# Alim.net
KiCad netlist of a schematic drawn in Altium Designer
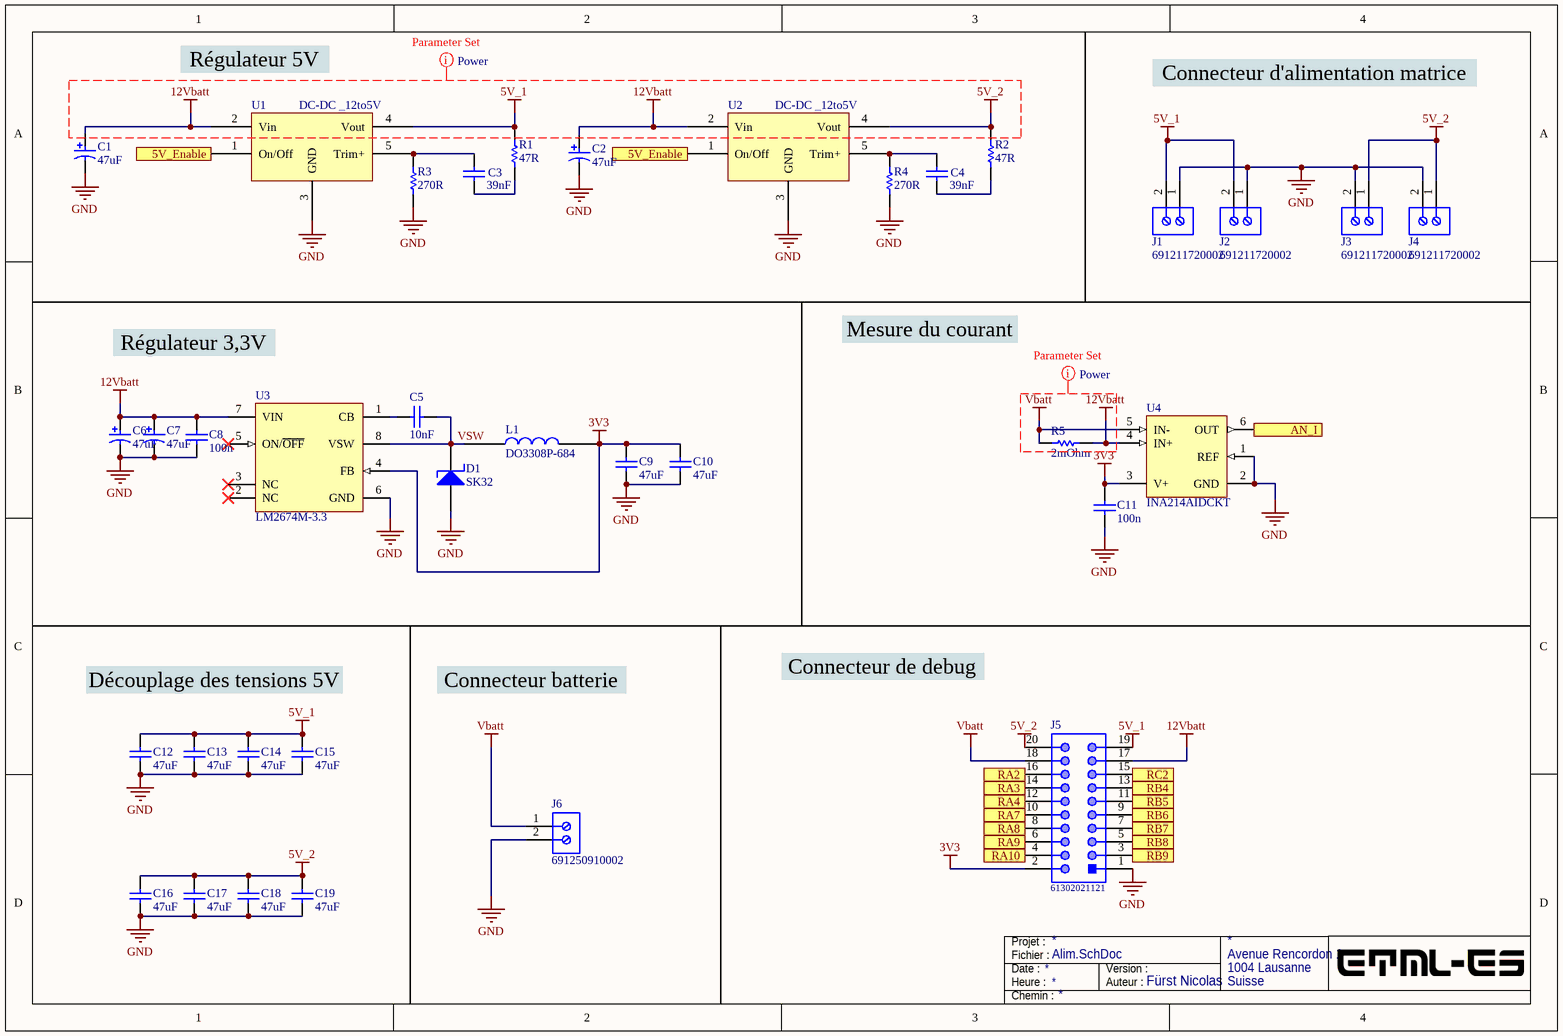
[diagram p0: Alim.SchDoc]

(export (version "E")
  (design (tool "Eeschema 10.0.6"))
  (components
    (comp (ref "C1")
      (value "47uF")
      (footprint "Capacitor")
      (fields (field (name "TOLERANCE") "20%") (field (name "MANUFACTURER") "Panasonic"))
      (libsource (lib "Schlib1") (part "CMP-2000-06221-1"))
    )
    (comp (ref "C2")
      (value "47uF")
      (footprint "Capacitor")
      (fields (field (name "TOLERANCE") "20%") (field (name "MANUFACTURER") "Panasonic"))
      (libsource (lib "Schlib1") (part "CMP-2000-06221-1"))
    )
    (comp (ref "C3")
      (value "39nF")
      (footprint "CAPC0805(2012)155_L")
      (fields (field (name "TOLERANCE") "Â±10%"))
      (libsource (lib "Schlib1") (part "Capa"))
    )
    (comp (ref "C4")
      (value "39nF")
      (footprint "CAPC0805(2012)155_L")
      (fields (field (name "TOLERANCE") "Â±10%"))
      (libsource (lib "Schlib1") (part "Capa"))
    )
    (comp (ref "C5")
      (value "10nF")
      (footprint "CAPC0805(2012)155_L")
      (fields (field (name "TOLERANCE") "Â±10%"))
      (libsource (lib "Schlib1") (part "Capa"))
    )
    (comp (ref "C6")
      (value "47uF")
      (footprint "Capacitor")
      (fields (field (name "TOLERANCE") "20%") (field (name "MANUFACTURER") "Panasonic"))
      (libsource (lib "Schlib1") (part "CMP-2000-06221-1"))
    )
    (comp (ref "C7")
      (value "47uF")
      (footprint "Capacitor")
      (fields (field (name "TOLERANCE") "20%") (field (name "MANUFACTURER") "Panasonic"))
      (libsource (lib "Schlib1") (part "CMP-2000-06221-1"))
    )
    (comp (ref "C8")
      (value "100n")
      (footprint "CAPC0805(2012)155_L")
      (fields (field (name "TOLERANCE") "Â±10%"))
      (libsource (lib "Schlib1") (part "Capa"))
    )
    (comp (ref "C9")
      (value "47uF")
      (footprint "CAPC1206(3216)190_N")
      (description "CAP 47uF 10V ±20% 1206 (3216 Metric) Thickness 1.9mm SMD")
      (fields (field (name "TOLERANCE") "Â±20%"))
      (libsource (lib "Altium Content Vault") (part "CAP"))
    )
    (comp (ref "C10")
      (value "47uF")
      (footprint "CAPC1206(3216)190_N")
      (description "CAP 47uF 10V ±20% 1206 (3216 Metric) Thickness 1.9mm SMD")
      (fields (field (name "TOLERANCE") "Â±20%"))
      (libsource (lib "Altium Content Vault") (part "CAP"))
    )
    (comp (ref "C11")
      (value "100n")
      (footprint "CAPC0805(2012)155_L")
      (fields (field (name "TOLERANCE") "Â±10%"))
      (libsource (lib "Schlib1") (part "Capa"))
    )
    (comp (ref "C12")
      (value "47uF")
      (footprint "CAPC1206(3216)190_N")
      (description "CAP 47uF 10V ±20% 1206 (3216 Metric) Thickness 1.9mm SMD")
      (fields (field (name "TOLERANCE") "Â±20%"))
      (libsource (lib "Altium Content Vault") (part "CAP"))
    )
    (comp (ref "C13")
      (value "47uF")
      (footprint "CAPC1206(3216)190_N")
      (description "CAP 47uF 10V ±20% 1206 (3216 Metric) Thickness 1.9mm SMD")
      (fields (field (name "TOLERANCE") "Â±20%"))
      (libsource (lib "Altium Content Vault") (part "CAP"))
    )
    (comp (ref "C14")
      (value "47uF")
      (footprint "CAPC1206(3216)190_N")
      (description "CAP 47uF 10V ±20% 1206 (3216 Metric) Thickness 1.9mm SMD")
      (fields (field (name "TOLERANCE") "Â±20%"))
      (libsource (lib "Altium Content Vault") (part "CAP"))
    )
    (comp (ref "C15")
      (value "47uF")
      (footprint "CAPC1206(3216)190_N")
      (description "CAP 47uF 10V ±20% 1206 (3216 Metric) Thickness 1.9mm SMD")
      (fields (field (name "TOLERANCE") "Â±20%"))
      (libsource (lib "Altium Content Vault") (part "CAP"))
    )
    (comp (ref "C16")
      (value "47uF")
      (footprint "CAPC1206(3216)190_N")
      (description "CAP 47uF 10V ±20% 1206 (3216 Metric) Thickness 1.9mm SMD")
      (fields (field (name "TOLERANCE") "Â±20%"))
      (libsource (lib "Altium Content Vault") (part "CAP"))
    )
    (comp (ref "C17")
      (value "47uF")
      (footprint "CAPC1206(3216)190_N")
      (description "CAP 47uF 10V ±20% 1206 (3216 Metric) Thickness 1.9mm SMD")
      (fields (field (name "TOLERANCE") "Â±20%"))
      (libsource (lib "Altium Content Vault") (part "CAP"))
    )
    (comp (ref "C18")
      (value "47uF")
      (footprint "CAPC1206(3216)190_N")
      (description "CAP 47uF 10V ±20% 1206 (3216 Metric) Thickness 1.9mm SMD")
      (fields (field (name "TOLERANCE") "Â±20%"))
      (libsource (lib "Altium Content Vault") (part "CAP"))
    )
    (comp (ref "C19")
      (value "47uF")
      (footprint "CAPC1206(3216)190_N")
      (description "CAP 47uF 10V ±20% 1206 (3216 Metric) Thickness 1.9mm SMD")
      (fields (field (name "TOLERANCE") "Â±20%"))
      (libsource (lib "Altium Content Vault") (part "CAP"))
    )
    (comp (ref "D1")
      (value "SK32")
      (footprint "DO-214AC")
      (description "Shotky diod")
      (fields (field (name "PARTNUMBER") "151031SS04000") (field (name "MANUFACTURER") "Wuerth Elektronik"))
      (libsource (lib "Schlib1") (part "SK32"))
    )
    (comp (ref "J1")
      (value "691211720002")
      (footprint "691211720002")
      (description "Serie 211 - 5.00 mm 45deg Entry Modular with Rising Cage Clamp - 15.50 mm Height WR-TBL, 2 pin")
      (fields (field (name "MANUFACTURER") "Wurth Elektronik") (field (name "PUBLISHER") "WurthElektronik"))
      (libsource (lib "Altium Content Vault") (part "WE-CN-1P-F-TB2"))
    )
    (comp (ref "J2")
      (value "691211720002")
      (footprint "691211720002")
      (description "Serie 211 - 5.00 mm 45deg Entry Modular with Rising Cage Clamp - 15.50 mm Height WR-TBL, 2 pin")
      (fields (field (name "MANUFACTURER") "Wurth Elektronik") (field (name "PUBLISHER") "WurthElektronik"))
      (libsource (lib "Altium Content Vault") (part "WE-CN-1P-F-TB2"))
    )
    (comp (ref "J3")
      (value "691211720002")
      (footprint "691211720002")
      (description "Serie 211 - 5.00 mm 45deg Entry Modular with Rising Cage Clamp - 15.50 mm Height WR-TBL, 2 pin")
      (fields (field (name "MANUFACTURER") "Wurth Elektronik") (field (name "PUBLISHER") "WurthElektronik"))
      (libsource (lib "Altium Content Vault") (part "WE-CN-1P-F-TB2"))
    )
    (comp (ref "J4")
      (value "691211720002")
      (footprint "691211720002")
      (description "Serie 211 - 5.00 mm 45deg Entry Modular with Rising Cage Clamp - 15.50 mm Height WR-TBL, 2 pin")
      (fields (field (name "MANUFACTURER") "Wurth Elektronik") (field (name "PUBLISHER") "WurthElektronik"))
      (libsource (lib "Altium Content Vault") (part "WE-CN-1P-F-TB2"))
    )
    (comp (ref "J5")
      (value "61302021121")
      (footprint "61302021121")
      (description "THT Vertical Pin Header WR-PHD, Pitch 2.54 mm, Dual Row, 20 pins")
      (fields (field (name "MANUFACTURER") "Wurth Elektronik") (field (name "PUBLISHER") "WurthElektronik"))
      (libsource (lib "Altium Content Vault") (part "WE-CN-2P-M-R20"))
    )
    (comp (ref "J6")
      (value "691250910002")
      (footprint "691250910002")
      (description "Serie 2509 - 9.52 mm Horizontal Entry Modular with Rising Cage Clamp WR-TBL, 2 pin")
      (fields (field (name "MANUFACTURER") "Wurth Elektronik") (field (name "PUBLISHER") "WurthElektronik"))
      (libsource (lib "Altium Content Vault") (part "WE-CN-1P-F-TB2"))
    )
    (comp (ref "L1")
      (value "DO3308P-684")
      (footprint "DO3308P")
      (libsource (lib "Schlib1") (part "DO3308P-684"))
    )
    (comp (ref "R1")
      (value "47R")
      (footprint "RESC0805(2012)_N")
      (fields (field (name "POWER") "0.125 W") (field (name "TOLERANCE") "1 %"))
      (libsource (lib "Schlib1") (part "Resistor"))
    )
    (comp (ref "R2")
      (value "47R")
      (footprint "RESC0805(2012)_N")
      (fields (field (name "POWER") "0.125 W") (field (name "TOLERANCE") "1 %"))
      (libsource (lib "Schlib1") (part "Resistor"))
    )
    (comp (ref "R3")
      (value "270R")
      (footprint "RESC0805(2012)_N")
      (fields (field (name "POWER") "0.125 W") (field (name "TOLERANCE") "1 %"))
      (libsource (lib "Schlib1") (part "Resistor"))
    )
    (comp (ref "R4")
      (value "270R")
      (footprint "RESC0805(2012)_N")
      (fields (field (name "POWER") "0.125 W") (field (name "TOLERANCE") "1 %"))
      (libsource (lib "Schlib1") (part "Resistor"))
    )
    (comp (ref "R5")
      (value "2mOhm")
      (footprint "RESC1206(3216)_N")
      (fields (field (name "POWER") "0.125 W") (field (name "TOLERANCE") "1 %"))
      (libsource (lib "Schlib1") (part "Resistor"))
    )
    (comp (ref "U1")
      (value "DC-DC _12to5V")
      (footprint "DC-DC")
      (libsource (lib "Schlib1") (part "DC-DC _12to5V"))
    )
    (comp (ref "U2")
      (value "DC-DC _12to5V")
      (footprint "DC-DC")
      (libsource (lib "Schlib1") (part "DC-DC _12to5V"))
    )
    (comp (ref "U3")
      (value "LM2674M-3.3")
      (footprint "M08A_N")
      (fields (field (name "MANUFACTURER") "National Semiconductor"))
      (libsource (lib "Altium Content Vault") (part "PM-REG-LM2674"))
    )
    (comp (ref "U4")
      (value "INA214AIDCKT")
      (footprint "DCK0006A_N")
      (fields (field (name "MANUFACTURER") "TexasInstruments"))
      (libsource (lib "Schlib1") (part "CMP-2000-06456-1"))
    )
  )
  (nets
    (net (code "1") (name "/5V_Enable") (class "Default")
      (node (ref "U1") (pin "1") (pinfunction "On/Off_1") (pintype "passive"))
      (node (ref "U2") (pin "1") (pinfunction "On/Off_1") (pintype "passive"))
    )
    (net (code "2") (name "/AN_I") (class "Default")
      (node (ref "U4") (pin "6") (pinfunction "OUT_6") (pintype "output"))
    )
    (net (code "3") (name "/RA2") (class "Default")
      (node (ref "J5") (pin "16") (pinfunction "16_16") (pintype "passive"))
    )
    (net (code "4") (name "/RA3") (class "Default")
      (node (ref "J5") (pin "14") (pinfunction "14_14") (pintype "passive"))
    )
    (net (code "5") (name "/RA4") (class "Default")
      (node (ref "J5") (pin "12") (pinfunction "12_12") (pintype "passive"))
    )
    (net (code "6") (name "/RA7") (class "Default")
      (node (ref "J5") (pin "10") (pinfunction "10_10") (pintype "passive"))
    )
    (net (code "7") (name "/RA8") (class "Default")
      (node (ref "J5") (pin "8") (pinfunction "8_8") (pintype "passive"))
    )
    (net (code "8") (name "/RA9") (class "Default")
      (node (ref "J5") (pin "6") (pinfunction "6_6") (pintype "passive"))
    )
    (net (code "9") (name "/RA10") (class "Default")
      (node (ref "J5") (pin "4") (pinfunction "4_4") (pintype "passive"))
    )
    (net (code "10") (name "/RB4") (class "Default")
      (node (ref "J5") (pin "13") (pinfunction "13_13") (pintype "passive"))
    )
    (net (code "11") (name "/RB5") (class "Default")
      (node (ref "J5") (pin "11") (pinfunction "11_11") (pintype "passive"))
    )
    (net (code "12") (name "/RB6") (class "Default")
      (node (ref "J5") (pin "9") (pinfunction "9_9") (pintype "passive"))
    )
    (net (code "13") (name "/RB7") (class "Default")
      (node (ref "J5") (pin "7") (pinfunction "7_7") (pintype "passive"))
    )
    (net (code "14") (name "/RB8") (class "Default")
      (node (ref "J5") (pin "5") (pinfunction "5_5") (pintype "passive"))
    )
    (net (code "15") (name "/RB9") (class "Default")
      (node (ref "J5") (pin "3") (pinfunction "3_3") (pintype "passive"))
    )
    (net (code "16") (name "/RC2") (class "Default")
      (node (ref "J5") (pin "15") (pinfunction "15_15") (pintype "passive"))
    )
    (net (code "17") (name "/VSW") (class "Default")
      (node (ref "C5") (pin "2") (pinfunction "2_2") (pintype "passive"))
      (node (ref "D1") (pin "1") (pinfunction "K_1") (pintype "passive"))
      (node (ref "L1") (pin "1") (pintype "passive"))
      (node (ref "U3") (pin "8") (pinfunction "VSW_8") (pintype "power_in"))
    )
    (net (code "18") (name "3V3") (class "Default")
      (node (ref "C10") (pin "2") (pinfunction "2_2") (pintype "passive"))
      (node (ref "C11") (pin "1") (pinfunction "1_1") (pintype "passive"))
      (node (ref "C9") (pin "2") (pinfunction "2_2") (pintype "passive"))
      (node (ref "J5") (pin "2") (pinfunction "2_2") (pintype "passive"))
      (node (ref "L1") (pin "2") (pintype "passive"))
      (node (ref "U3") (pin "4") (pinfunction "FB_4") (pintype "input"))
      (node (ref "U4") (pin "3") (pinfunction "V+_3") (pintype "power_in"))
    )
    (net (code "19") (name "5V_1") (class "Default")
      (node (ref "C12") (pin "2") (pinfunction "2_2") (pintype "passive"))
      (node (ref "C13") (pin "2") (pinfunction "2_2") (pintype "passive"))
      (node (ref "C14") (pin "2") (pinfunction "2_2") (pintype "passive"))
      (node (ref "C15") (pin "2") (pinfunction "2_2") (pintype "passive"))
      (node (ref "J1") (pin "2") (pinfunction "2_2") (pintype "passive"))
      (node (ref "J2") (pin "2") (pinfunction "2_2") (pintype "passive"))
      (node (ref "J5") (pin "19") (pinfunction "19_19") (pintype "passive"))
      (node (ref "R1") (pin "2") (pinfunction "2_2") (pintype "passive"))
      (node (ref "U1") (pin "4") (pinfunction "Vout_4") (pintype "passive"))
    )
    (net (code "20") (name "5V_2") (class "Default")
      (node (ref "C16") (pin "2") (pinfunction "2_2") (pintype "passive"))
      (node (ref "C17") (pin "2") (pinfunction "2_2") (pintype "passive"))
      (node (ref "C18") (pin "2") (pinfunction "2_2") (pintype "passive"))
      (node (ref "C19") (pin "2") (pinfunction "2_2") (pintype "passive"))
      (node (ref "J3") (pin "1") (pinfunction "1_1") (pintype "passive"))
      (node (ref "J4") (pin "1") (pinfunction "1_1") (pintype "passive"))
      (node (ref "J5") (pin "20") (pinfunction "20_20") (pintype "passive"))
      (node (ref "R2") (pin "2") (pinfunction "2_2") (pintype "passive"))
      (node (ref "U2") (pin "4") (pinfunction "Vout_4") (pintype "passive"))
    )
    (net (code "21") (name "12Vbatt") (class "Default")
      (node (ref "C1") (pin "1") (pinfunction "1_1") (pintype "passive"))
      (node (ref "C2") (pin "1") (pinfunction "1_1") (pintype "passive"))
      (node (ref "C6") (pin "1") (pinfunction "1_1") (pintype "passive"))
      (node (ref "C7") (pin "1") (pinfunction "1_1") (pintype "passive"))
      (node (ref "C8") (pin "1") (pinfunction "1_1") (pintype "passive"))
      (node (ref "J5") (pin "17") (pinfunction "17_17") (pintype "passive"))
      (node (ref "R5") (pin "1") (pinfunction "1_1") (pintype "passive"))
      (node (ref "U1") (pin "2") (pinfunction "Vin_2") (pintype "passive"))
      (node (ref "U2") (pin "2") (pinfunction "Vin_2") (pintype "passive"))
      (node (ref "U3") (pin "7") (pinfunction "VIN_7") (pintype "power_in"))
      (node (ref "U4") (pin "4") (pinfunction "IN+_4") (pintype "input"))
    )
    (net (code "22") (name "GND") (class "Default")
      (node (ref "C1") (pin "2") (pinfunction "2_2") (pintype "passive"))
      (node (ref "C10") (pin "1") (pinfunction "1_1") (pintype "passive"))
      (node (ref "C11") (pin "2") (pinfunction "2_2") (pintype "passive"))
      (node (ref "C12") (pin "1") (pinfunction "1_1") (pintype "passive"))
      (node (ref "C13") (pin "1") (pinfunction "1_1") (pintype "passive"))
      (node (ref "C14") (pin "1") (pinfunction "1_1") (pintype "passive"))
      (node (ref "C15") (pin "1") (pinfunction "1_1") (pintype "passive"))
      (node (ref "C16") (pin "1") (pinfunction "1_1") (pintype "passive"))
      (node (ref "C17") (pin "1") (pinfunction "1_1") (pintype "passive"))
      (node (ref "C18") (pin "1") (pinfunction "1_1") (pintype "passive"))
      (node (ref "C19") (pin "1") (pinfunction "1_1") (pintype "passive"))
      (node (ref "C2") (pin "2") (pinfunction "2_2") (pintype "passive"))
      (node (ref "C6") (pin "2") (pinfunction "2_2") (pintype "passive"))
      (node (ref "C7") (pin "2") (pinfunction "2_2") (pintype "passive"))
      (node (ref "C8") (pin "2") (pinfunction "2_2") (pintype "passive"))
      (node (ref "C9") (pin "1") (pinfunction "1_1") (pintype "passive"))
      (node (ref "D1") (pin "2") (pinfunction "A_2") (pintype "passive"))
      (node (ref "J1") (pin "1") (pinfunction "1_1") (pintype "passive"))
      (node (ref "J2") (pin "1") (pinfunction "1_1") (pintype "passive"))
      (node (ref "J3") (pin "2") (pinfunction "2_2") (pintype "passive"))
      (node (ref "J4") (pin "2") (pinfunction "2_2") (pintype "passive"))
      (node (ref "J5") (pin "1") (pinfunction "1_1") (pintype "passive"))
      (node (ref "J6") (pin "2") (pinfunction "2_2") (pintype "passive"))
      (node (ref "R3") (pin "1") (pinfunction "1_1") (pintype "passive"))
      (node (ref "R4") (pin "1") (pinfunction "1_1") (pintype "passive"))
      (node (ref "U1") (pin "3") (pinfunction "GND_3") (pintype "passive"))
      (node (ref "U2") (pin "3") (pinfunction "GND_3") (pintype "passive"))
      (node (ref "U3") (pin "6") (pinfunction "GND_6") (pintype "power_in"))
      (node (ref "U4") (pin "1") (pinfunction "REF_1") (pintype "input"))
      (node (ref "U4") (pin "2") (pinfunction "GND_2") (pintype "power_in"))
    )
    (net (code "23") (name "Net-(C3-Pad2)") (class "Default")
      (node (ref "C3") (pin "2") (pinfunction "2_2") (pintype "passive"))
      (node (ref "R1") (pin "1") (pinfunction "1_1") (pintype "passive"))
    )
    (net (code "24") (name "Net-(C4-Pad1)") (class "Default")
      (node (ref "C4") (pin "1") (pinfunction "1_1") (pintype "passive"))
      (node (ref "R2") (pin "1") (pinfunction "1_1") (pintype "passive"))
    )
    (net (code "25") (name "Net-(U1-Trim+)") (class "Default")
      (node (ref "C3") (pin "1") (pinfunction "1_1") (pintype "passive"))
      (node (ref "R3") (pin "2") (pinfunction "2_2") (pintype "passive"))
      (node (ref "U1") (pin "5") (pinfunction "Trim+_5") (pintype "passive"))
    )
    (net (code "26") (name "Net-(U2-Trim+)") (class "Default")
      (node (ref "C4") (pin "2") (pinfunction "2_2") (pintype "passive"))
      (node (ref "R4") (pin "2") (pinfunction "2_2") (pintype "passive"))
      (node (ref "U2") (pin "5") (pinfunction "Trim+_5") (pintype "passive"))
    )
    (net (code "27") (name "Net-(U3-CB)") (class "Default")
      (node (ref "C5") (pin "1") (pinfunction "1_1") (pintype "passive"))
      (node (ref "U3") (pin "1") (pinfunction "CB_1") (pintype "passive"))
    )
    (net (code "28") (name "Vbatt") (class "Default")
      (node (ref "J5") (pin "18") (pinfunction "18_18") (pintype "passive"))
      (node (ref "J6") (pin "1") (pinfunction "1_1") (pintype "passive"))
      (node (ref "R5") (pin "2") (pinfunction "2_2") (pintype "passive"))
      (node (ref "U4") (pin "5") (pinfunction "IN-_5") (pintype "input"))
    )
    (net (code "29") (name "unconnected-(U3-NC-Pad2)") (class "Default")
      (node (ref "U3") (pin "2") (pinfunction "NC_2") (pintype "passive+no_connect"))
    )
    (net (code "30") (name "unconnected-(U3-NC-Pad3)") (class "Default")
      (node (ref "U3") (pin "3") (pinfunction "NC_3") (pintype "passive+no_connect"))
    )
    (net (code "31") (name "unconnected-(U3-ON{slash}~{OFF}-Pad5)") (class "Default")
      (node (ref "U3") (pin "5") (pinfunction "ON/~{OFF}_5") (pintype "input+no_connect"))
    )
  )
)
